# ControlInputs.net
KiCad netlist of a schematic drawn in EAGLE
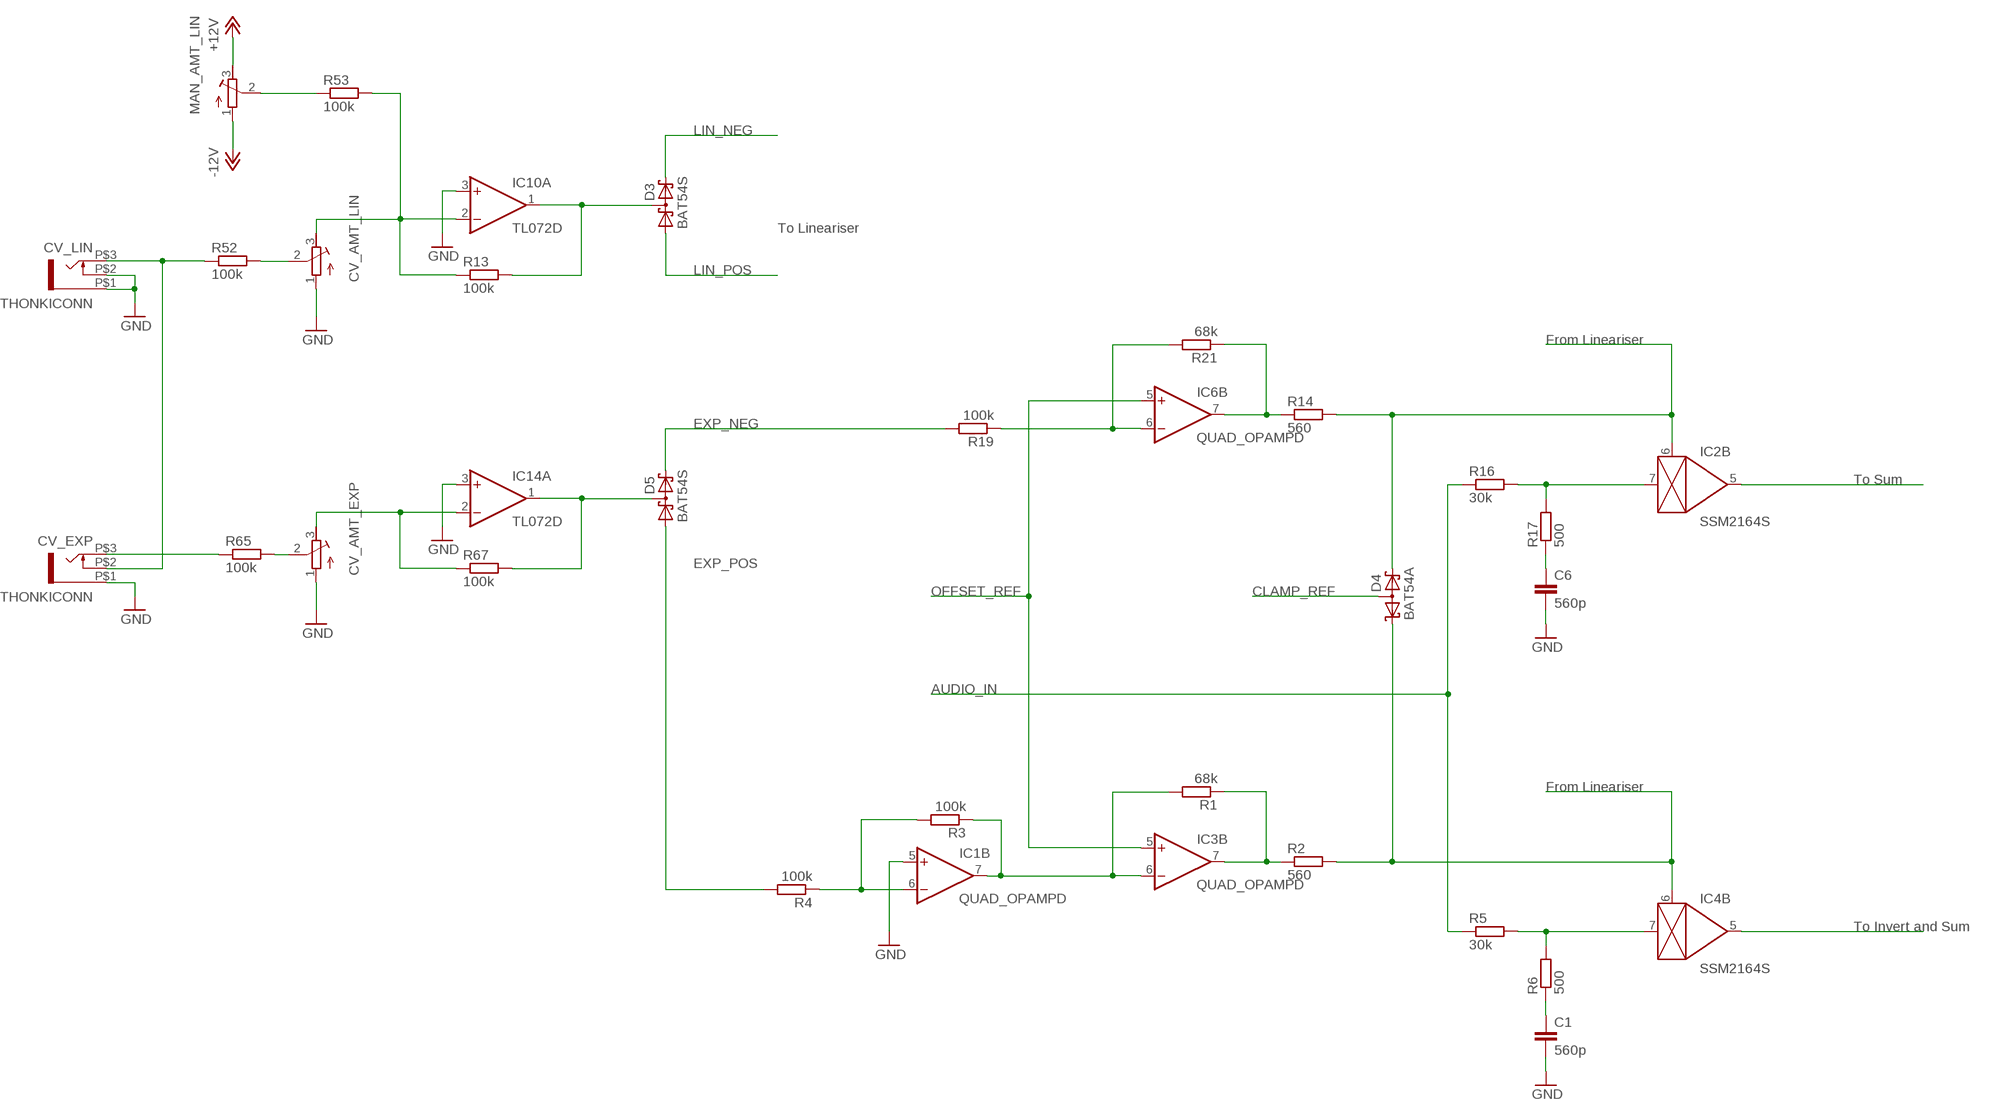
[diagram p0: schematic, sheet 1]

(export (version "E")
  (design (tool "Eeschema 10.0.6"))
  (components
    (comp (ref "C1")
      (value "560p")
      (footprint "eagle-import:C0603K")
      (libsource (lib "eagle-import") (part "C-EUC0603K"))
    )
    (comp (ref "C6")
      (value "560p")
      (footprint "eagle-import:C0603K")
      (libsource (lib "eagle-import") (part "C-EUC0603K"))
    )
    (comp (ref "CV_AMT_EXP")
      (value "R-TRIMM64X")
      (footprint "eagle-import:RTRIM64X")
      (libsource (lib "eagle-import") (part "R-TRIMM64X"))
    )
    (comp (ref "CV_AMT_LIN")
      (value "R-TRIMM64X")
      (footprint "eagle-import:RTRIM64X")
      (libsource (lib "eagle-import") (part "R-TRIMM64X"))
    )
    (comp (ref "CV_EXP")
      (value "THONKICONN")
      (footprint "eagle-import:THONKICONN")
      (libsource (lib "eagle-import") (part "THONKICONN"))
    )
    (comp (ref "CV_LIN")
      (value "THONKICONN")
      (footprint "eagle-import:THONKICONN")
      (libsource (lib "eagle-import") (part "THONKICONN"))
    )
    (comp (ref "D3")
      (value "BAT54S")
      (footprint "eagle-import:SOT23")
      (libsource (lib "eagle-import") (part "BAT54S"))
    )
    (comp (ref "D4")
      (value "BAT54A")
      (footprint "eagle-import:SOT23")
      (libsource (lib "eagle-import") (part "BAT54A"))
    )
    (comp (ref "D5")
      (value "BAT54S")
      (footprint "eagle-import:SOT23")
      (libsource (lib "eagle-import") (part "BAT54S"))
    )
    (comp (ref "IC1")
      (value "QUAD_OPAMPD")
      (footprint "eagle-import:SO14")
      (libsource (lib "eagle-import") (part "QUAD_OPAMPD"))
    )
    (comp (ref "IC2")
      (value "SSM2164S")
      (footprint "eagle-import:SOIC16N")
      (libsource (lib "eagle-import") (part "SSM2164S"))
    )
    (comp (ref "IC3")
      (value "QUAD_OPAMPD")
      (footprint "eagle-import:SO14")
      (libsource (lib "eagle-import") (part "QUAD_OPAMPD"))
    )
    (comp (ref "IC4")
      (value "SSM2164S")
      (footprint "eagle-import:SOIC16N")
      (libsource (lib "eagle-import") (part "SSM2164S"))
    )
    (comp (ref "IC6")
      (value "QUAD_OPAMPD")
      (footprint "eagle-import:SO14")
      (libsource (lib "eagle-import") (part "QUAD_OPAMPD"))
    )
    (comp (ref "IC10")
      (value "TL072D")
      (footprint "eagle-import:SO08")
      (libsource (lib "eagle-import") (part "TL072D"))
    )
    (comp (ref "IC14")
      (value "TL072D")
      (footprint "eagle-import:SO08")
      (libsource (lib "eagle-import") (part "TL072D"))
    )
    (comp (ref "MAN_AMT_LIN")
      (value "R-TRIMM64X")
      (footprint "eagle-import:RTRIM64X")
      (libsource (lib "eagle-import") (part "R-TRIMM64X"))
    )
    (comp (ref "R1")
      (value "68k")
      (footprint "eagle-import:0603")
      (libsource (lib "eagle-import") (part "R-EU_0603"))
    )
    (comp (ref "R2")
      (value "560")
      (footprint "eagle-import:0603")
      (libsource (lib "eagle-import") (part "R-EU_0603"))
    )
    (comp (ref "R3")
      (value "100k")
      (footprint "eagle-import:0603")
      (libsource (lib "eagle-import") (part "R-EU_0603"))
    )
    (comp (ref "R4")
      (value "100k")
      (footprint "eagle-import:0603")
      (libsource (lib "eagle-import") (part "R-EU_0603"))
    )
    (comp (ref "R5")
      (value "30k")
      (footprint "eagle-import:0603")
      (libsource (lib "eagle-import") (part "R-EU_0603"))
    )
    (comp (ref "R6")
      (value "500")
      (footprint "eagle-import:0603")
      (libsource (lib "eagle-import") (part "R-EU_0603"))
    )
    (comp (ref "R13")
      (value "100k")
      (footprint "eagle-import:0603")
      (libsource (lib "eagle-import") (part "R-EU_0603"))
    )
    (comp (ref "R14")
      (value "560")
      (footprint "eagle-import:0603")
      (libsource (lib "eagle-import") (part "R-EU_0603"))
    )
    (comp (ref "R16")
      (value "30k")
      (footprint "eagle-import:0603")
      (libsource (lib "eagle-import") (part "R-EU_0603"))
    )
    (comp (ref "R17")
      (value "500")
      (footprint "eagle-import:0603")
      (libsource (lib "eagle-import") (part "R-EU_0603"))
    )
    (comp (ref "R19")
      (value "100k")
      (footprint "eagle-import:0603")
      (libsource (lib "eagle-import") (part "R-EU_0603"))
    )
    (comp (ref "R21")
      (value "68k")
      (footprint "eagle-import:0603")
      (libsource (lib "eagle-import") (part "R-EU_0603"))
    )
    (comp (ref "R52")
      (value "100k")
      (footprint "eagle-import:0603")
      (libsource (lib "eagle-import") (part "R-EU_0603"))
    )
    (comp (ref "R53")
      (value "100k")
      (footprint "eagle-import:0603")
      (libsource (lib "eagle-import") (part "R-EU_0603"))
    )
    (comp (ref "R65")
      (value "100k")
      (footprint "eagle-import:0603")
      (libsource (lib "eagle-import") (part "R-EU_0603"))
    )
    (comp (ref "R67")
      (value "100k")
      (footprint "eagle-import:0603")
      (libsource (lib "eagle-import") (part "R-EU_0603"))
    )
  )
  (nets
    (net (code "1") (name "+12V") (class "Default")
      (node (ref "MAN_AMT_LIN") (pin "3") (pinfunction "E_3") (pintype "passive"))
    )
    (net (code "2") (name "-12V") (class "Default")
      (node (ref "MAN_AMT_LIN") (pin "1") (pinfunction "A_1") (pintype "passive"))
    )
    (net (code "3") (name "/AUDIO_IN") (class "Default")
      (node (ref "R16") (pin "1") (pinfunction "1_1") (pintype "passive"))
      (node (ref "R5") (pin "1") (pinfunction "1_1") (pintype "passive"))
    )
    (net (code "4") (name "/CLAMP_REF") (class "Default")
      (node (ref "D4") (pin "3") (pinfunction "AA_3") (pintype "passive"))
    )
    (net (code "5") (name "/EXP_NEG") (class "Default")
      (node (ref "D5") (pin "2") (pinfunction "C2_2") (pintype "passive"))
      (node (ref "R19") (pin "2") (pinfunction "2_2") (pintype "passive"))
    )
    (net (code "6") (name "/EXP_POS") (class "Default")
      (node (ref "D5") (pin "1") (pinfunction "A1_1") (pintype "passive"))
      (node (ref "R4") (pin "2") (pinfunction "2_2") (pintype "passive"))
    )
    (net (code "7") (name "/LIN_NEG") (class "Default")
      (node (ref "D3") (pin "2") (pinfunction "C2_2") (pintype "passive"))
    )
    (net (code "8") (name "/LIN_POS") (class "Default")
      (node (ref "D3") (pin "1") (pinfunction "A1_1") (pintype "passive"))
    )
    (net (code "9") (name "/OFFSET_REF") (class "Default")
      (node (ref "IC3") (pin "5") (pinfunction "+IN_5") (pintype "input"))
      (node (ref "IC6") (pin "5") (pinfunction "+IN_5") (pintype "input"))
    )
    (net (code "10") (name "GND") (class "Default")
      (node (ref "C1") (pin "2") (pinfunction "2_2") (pintype "passive"))
      (node (ref "C6") (pin "2") (pinfunction "2_2") (pintype "passive"))
      (node (ref "CV_AMT_EXP") (pin "1") (pinfunction "A_1") (pintype "passive"))
      (node (ref "CV_AMT_LIN") (pin "1") (pinfunction "A_1") (pintype "passive"))
      (node (ref "CV_EXP") (pin "P$1") (pinfunction "5_P$1") (pintype "passive"))
      (node (ref "CV_LIN") (pin "P$1") (pinfunction "5_P$1") (pintype "passive"))
      (node (ref "CV_LIN") (pin "P$2") (pinfunction "4_P$2") (pintype "passive"))
      (node (ref "IC1") (pin "5") (pinfunction "+IN_5") (pintype "input"))
      (node (ref "IC10") (pin "3") (pinfunction "+IN_3") (pintype "input"))
      (node (ref "IC14") (pin "3") (pinfunction "+IN_3") (pintype "input"))
    )
    (net (code "11") (name "Net-(C1-Pad1)") (class "Default")
      (node (ref "C1") (pin "1") (pinfunction "1_1") (pintype "passive"))
      (node (ref "R6") (pin "1") (pinfunction "1_1") (pintype "passive"))
    )
    (net (code "12") (name "Net-(C6-Pad1)") (class "Default")
      (node (ref "C6") (pin "1") (pinfunction "1_1") (pintype "passive"))
      (node (ref "R17") (pin "1") (pinfunction "1_1") (pintype "passive"))
    )
    (net (code "13") (name "Net-(CV_AMT_EXP-E)") (class "Default")
      (node (ref "CV_AMT_EXP") (pin "3") (pinfunction "E_3") (pintype "passive"))
      (node (ref "IC14") (pin "2") (pinfunction "-IN_2") (pintype "input"))
      (node (ref "R67") (pin "1") (pinfunction "1_1") (pintype "passive"))
    )
    (net (code "14") (name "Net-(CV_AMT_EXP-S)") (class "Default")
      (node (ref "CV_AMT_EXP") (pin "2") (pinfunction "S_2") (pintype "passive"))
      (node (ref "R65") (pin "2") (pinfunction "2_2") (pintype "passive"))
    )
    (net (code "15") (name "Net-(CV_AMT_LIN-E)") (class "Default")
      (node (ref "CV_AMT_LIN") (pin "3") (pinfunction "E_3") (pintype "passive"))
      (node (ref "IC10") (pin "2") (pinfunction "-IN_2") (pintype "input"))
      (node (ref "R13") (pin "1") (pinfunction "1_1") (pintype "passive"))
      (node (ref "R53") (pin "2") (pinfunction "2_2") (pintype "passive"))
    )
    (net (code "16") (name "Net-(CV_AMT_LIN-S)") (class "Default")
      (node (ref "CV_AMT_LIN") (pin "2") (pinfunction "S_2") (pintype "passive"))
      (node (ref "R52") (pin "2") (pinfunction "2_2") (pintype "passive"))
    )
    (net (code "17") (name "Net-(CV_EXP-3)") (class "Default")
      (node (ref "CV_EXP") (pin "P$3") (pinfunction "3_P$3") (pintype "passive"))
      (node (ref "R65") (pin "1") (pinfunction "1_1") (pintype "passive"))
    )
    (net (code "18") (name "Net-(CV_EXP-4)") (class "Default")
      (node (ref "CV_EXP") (pin "P$2") (pinfunction "4_P$2") (pintype "passive"))
      (node (ref "CV_LIN") (pin "P$3") (pinfunction "3_P$3") (pintype "passive"))
      (node (ref "R52") (pin "1") (pinfunction "1_1") (pintype "passive"))
    )
    (net (code "19") (name "Net-(D3-C1A2)") (class "Default")
      (node (ref "D3") (pin "3") (pinfunction "C1A2_3") (pintype "passive"))
      (node (ref "IC10") (pin "1") (pinfunction "OUT_1") (pintype "output"))
      (node (ref "R13") (pin "2") (pinfunction "2_2") (pintype "passive"))
    )
    (net (code "20") (name "Net-(D4-K1)") (class "Default")
      (node (ref "D4") (pin "1") (pinfunction "K1_1") (pintype "passive"))
      (node (ref "IC4") (pin "6") (pinfunction "CTRL_6") (pintype "input"))
      (node (ref "R2") (pin "2") (pinfunction "2_2") (pintype "passive"))
    )
    (net (code "21") (name "Net-(D4-K2)") (class "Default")
      (node (ref "D4") (pin "2") (pinfunction "K2_2") (pintype "passive"))
      (node (ref "IC2") (pin "6") (pinfunction "CTRL_6") (pintype "input"))
      (node (ref "R14") (pin "2") (pinfunction "2_2") (pintype "passive"))
    )
    (net (code "22") (name "Net-(D5-C1A2)") (class "Default")
      (node (ref "D5") (pin "3") (pinfunction "C1A2_3") (pintype "passive"))
      (node (ref "IC14") (pin "1") (pinfunction "OUT_1") (pintype "output"))
      (node (ref "R67") (pin "2") (pinfunction "2_2") (pintype "passive"))
    )
    (net (code "23") (name "Net-(IC1B--IN)") (class "Default")
      (node (ref "IC1") (pin "6") (pinfunction "-IN_6") (pintype "input"))
      (node (ref "R3") (pin "2") (pinfunction "2_2") (pintype "passive"))
      (node (ref "R4") (pin "1") (pinfunction "1_1") (pintype "passive"))
    )
    (net (code "24") (name "Net-(IC1B-OUT)") (class "Default")
      (node (ref "IC1") (pin "7") (pinfunction "OUT_7") (pintype "output"))
      (node (ref "IC3") (pin "6") (pinfunction "-IN_6") (pintype "input"))
      (node (ref "R1") (pin "2") (pinfunction "2_2") (pintype "passive"))
      (node (ref "R3") (pin "1") (pinfunction "1_1") (pintype "passive"))
    )
    (net (code "25") (name "Net-(IC2B-IN)") (class "Default")
      (node (ref "IC2") (pin "7") (pinfunction "IN_7") (pintype "input"))
      (node (ref "R16") (pin "2") (pinfunction "2_2") (pintype "passive"))
      (node (ref "R17") (pin "2") (pinfunction "2_2") (pintype "passive"))
    )
    (net (code "26") (name "Net-(IC3B-OUT)") (class "Default")
      (node (ref "IC3") (pin "7") (pinfunction "OUT_7") (pintype "output"))
      (node (ref "R1") (pin "1") (pinfunction "1_1") (pintype "passive"))
      (node (ref "R2") (pin "1") (pinfunction "1_1") (pintype "passive"))
    )
    (net (code "27") (name "Net-(IC4B-IN)") (class "Default")
      (node (ref "IC4") (pin "7") (pinfunction "IN_7") (pintype "input"))
      (node (ref "R5") (pin "2") (pinfunction "2_2") (pintype "passive"))
      (node (ref "R6") (pin "2") (pinfunction "2_2") (pintype "passive"))
    )
    (net (code "28") (name "Net-(IC6B--IN)") (class "Default")
      (node (ref "IC6") (pin "6") (pinfunction "-IN_6") (pintype "input"))
      (node (ref "R19") (pin "1") (pinfunction "1_1") (pintype "passive"))
      (node (ref "R21") (pin "2") (pinfunction "2_2") (pintype "passive"))
    )
    (net (code "29") (name "Net-(IC6B-OUT)") (class "Default")
      (node (ref "IC6") (pin "7") (pinfunction "OUT_7") (pintype "output"))
      (node (ref "R14") (pin "1") (pinfunction "1_1") (pintype "passive"))
      (node (ref "R21") (pin "1") (pinfunction "1_1") (pintype "passive"))
    )
    (net (code "30") (name "Net-(MAN_AMT_LIN-S)") (class "Default")
      (node (ref "MAN_AMT_LIN") (pin "2") (pinfunction "S_2") (pintype "passive"))
      (node (ref "R53") (pin "1") (pinfunction "1_1") (pintype "passive"))
    )
    (net (code "31") (name "unconnected-(IC2B-OUT-Pad5)") (class "Default")
      (node (ref "IC2") (pin "5") (pinfunction "OUT_5") (pintype "output"))
    )
    (net (code "32") (name "unconnected-(IC4B-OUT-Pad5)") (class "Default")
      (node (ref "IC4") (pin "5") (pinfunction "OUT_5") (pintype "output"))
    )
  )
)
